# cube_bottom_3.net
KiCad netlist of a schematic drawn in EAGLE
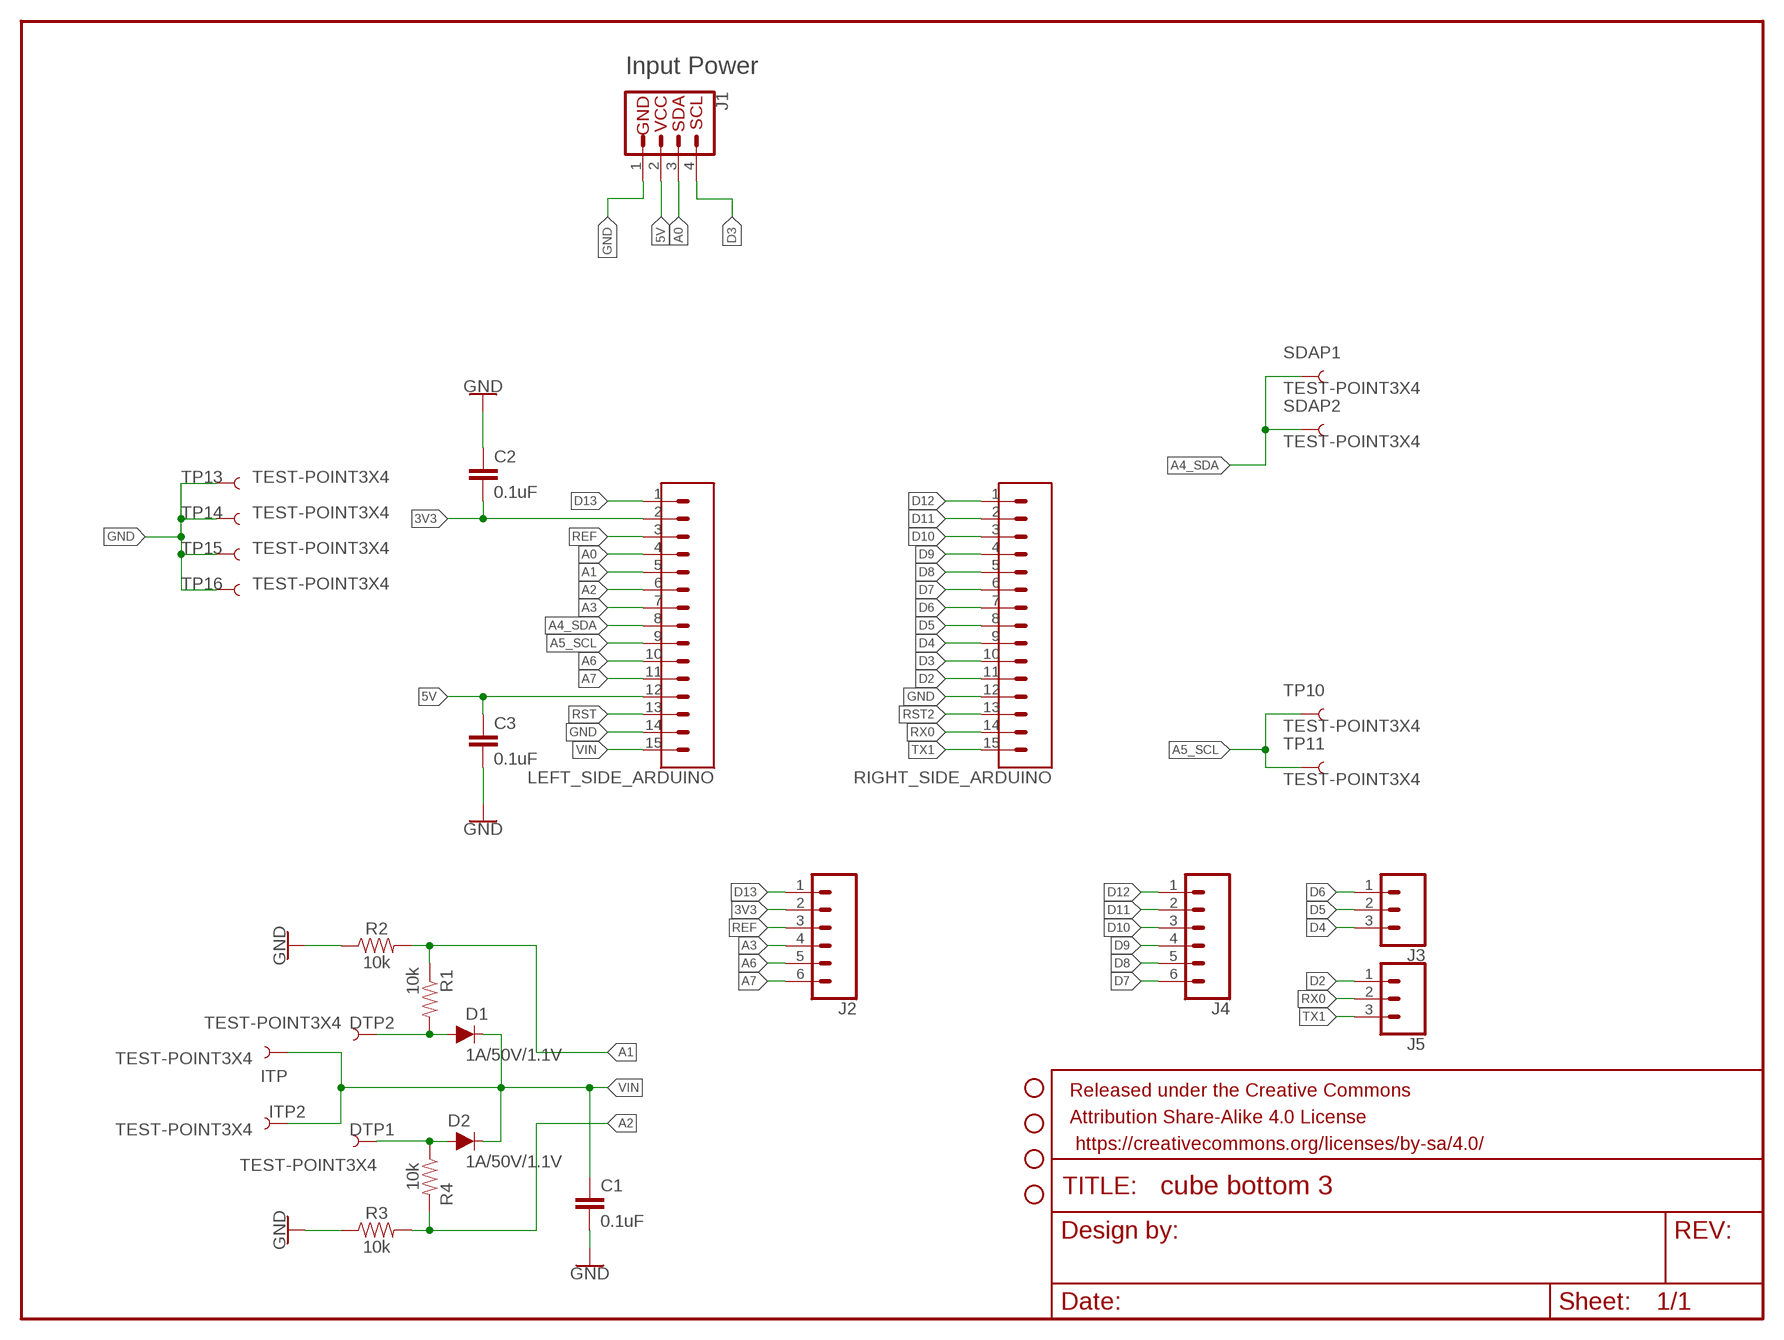
[diagram p0: schematic, sheet 1]

(export (version "E")
  (design (tool "Eeschema 10.0.6"))
  (components
    (comp (ref "C1")
      (value "0.1uF")
      (footprint "eagle-import:0603")
      (libsource (lib "eagle-import") (part "0.1UF-0603-25V-5%"))
    )
    (comp (ref "C2")
      (value "0.1uF")
      (footprint "eagle-import:0603")
      (libsource (lib "eagle-import") (part "0.1UF-0603-25V-(+80/-20%)"))
    )
    (comp (ref "C3")
      (value "0.1uF")
      (footprint "eagle-import:0603")
      (libsource (lib "eagle-import") (part "0.1UF-0603-25V-(+80/-20%)"))
    )
    (comp (ref "D1")
      (value "1A/50V/1.1V")
      (footprint "eagle-import:DIODE-1N4001")
      (libsource (lib "eagle-import") (part "DIODE-PTH"))
    )
    (comp (ref "D2")
      (value "1A/50V/1.1V")
      (footprint "eagle-import:DIODE-1N4001")
      (libsource (lib "eagle-import") (part "DIODE-PTH"))
    )
    (comp (ref "DTP1")
      (value "TEST-POINT3X4")
      (footprint "eagle-import:PAD.03X.04")
      (libsource (lib "eagle-import") (part "TEST-POINT3X4"))
    )
    (comp (ref "DTP2")
      (value "TEST-POINT3X4")
      (footprint "eagle-import:PAD.03X.04")
      (libsource (lib "eagle-import") (part "TEST-POINT3X4"))
    )
    (comp (ref "FRAME1")
      (value "FRAME-LETTERNO_PACKAGE")
      (footprint "eagle-import:DUMMY")
      (fields (field (name "DESIGNER") "Nobody"))
      (libsource (lib "eagle-import") (part "FRAME-LETTERNO_PACKAGE"))
    )
    (comp (ref "H1")
      (value "STAND-OFF")
      (footprint "eagle-import:STAND-OFF")
      (libsource (lib "eagle-import") (part "STAND-OFF"))
    )
    (comp (ref "H2")
      (value "STAND-OFF")
      (footprint "eagle-import:STAND-OFF")
      (libsource (lib "eagle-import") (part "STAND-OFF"))
    )
    (comp (ref "H3")
      (value "STAND-OFF")
      (footprint "eagle-import:STAND-OFF")
      (libsource (lib "eagle-import") (part "STAND-OFF"))
    )
    (comp (ref "H4")
      (value "STAND-OFF")
      (footprint "eagle-import:STAND-OFF")
      (libsource (lib "eagle-import") (part "STAND-OFF"))
    )
    (comp (ref "ITP")
      (value "TEST-POINT3X4")
      (footprint "eagle-import:PAD.03X.04")
      (libsource (lib "eagle-import") (part "TEST-POINT3X4"))
    )
    (comp (ref "ITP2")
      (value "TEST-POINT3X4")
      (footprint "eagle-import:PAD.03X.04")
      (libsource (lib "eagle-import") (part "TEST-POINT3X4"))
    )
    (comp (ref "J1")
      (value "QWIIC_CONNECTORJS-1MM")
      (footprint "eagle-import:1X04_1MM_RA")
      (libsource (lib "eagle-import") (part "QWIIC_CONNECTORJS-1MM"))
    )
    (comp (ref "J2")
      (value "CONN_06SILK_FEMALE_PTH")
      (footprint "eagle-import:1X06")
      (libsource (lib "eagle-import") (part "CONN_06SILK_FEMALE_PTH"))
    )
    (comp (ref "J3")
      (value "CONN_03")
      (footprint "eagle-import:1X03")
      (libsource (lib "eagle-import") (part "CONN_03"))
    )
    (comp (ref "J4")
      (value "CONN_06SILK_FEMALE_PTH")
      (footprint "eagle-import:1X06")
      (libsource (lib "eagle-import") (part "CONN_06SILK_FEMALE_PTH"))
    )
    (comp (ref "J5")
      (value "CONN_03")
      (footprint "eagle-import:1X03")
      (libsource (lib "eagle-import") (part "CONN_03"))
    )
    (comp (ref "LEFT_SIDE_ARDUINO")
      (value "CONN_06SMD_MALE")
      (footprint "eagle-import:1X15_SMD_MALE")
      (libsource (lib "eagle-import") (part "capstone footprints_CONN_06SMD_MALE"))
    )
    (comp (ref "R1")
      (value "10k")
      (footprint "eagle-import:0603")
      (libsource (lib "eagle-import") (part "10KOHM-0603-1/10W-1%"))
    )
    (comp (ref "R2")
      (value "10k")
      (footprint "eagle-import:0603")
      (libsource (lib "eagle-import") (part "10KOHM-0603-1/10W-1%"))
    )
    (comp (ref "R3")
      (value "10k")
      (footprint "eagle-import:0603")
      (libsource (lib "eagle-import") (part "10KOHM-0603-1/10W-1%"))
    )
    (comp (ref "R4")
      (value "10k")
      (footprint "eagle-import:0603")
      (libsource (lib "eagle-import") (part "10KOHM-0603-1/10W-1%"))
    )
    (comp (ref "RIGHT_SIDE_ARDUINO")
      (value "CONN_06SMD_MALE")
      (footprint "eagle-import:1X15_SMD_MALE")
      (libsource (lib "eagle-import") (part "capstone footprints_CONN_06SMD_MALE"))
    )
    (comp (ref "SDAP1")
      (value "TEST-POINT3X4")
      (footprint "eagle-import:PAD.03X.04")
      (libsource (lib "eagle-import") (part "TEST-POINT3X4"))
    )
    (comp (ref "SDAP2")
      (value "TEST-POINT3X4")
      (footprint "eagle-import:PAD.03X.04")
      (libsource (lib "eagle-import") (part "TEST-POINT3X4"))
    )
    (comp (ref "TP10")
      (value "TEST-POINT3X4")
      (footprint "eagle-import:PAD.03X.04")
      (libsource (lib "eagle-import") (part "TEST-POINT3X4"))
    )
    (comp (ref "TP11")
      (value "TEST-POINT3X4")
      (footprint "eagle-import:PAD.03X.04")
      (libsource (lib "eagle-import") (part "TEST-POINT3X4"))
    )
    (comp (ref "TP13")
      (value "TEST-POINT3X4")
      (footprint "eagle-import:PAD.03X.04")
      (libsource (lib "eagle-import") (part "TEST-POINT3X4"))
    )
    (comp (ref "TP14")
      (value "TEST-POINT3X4")
      (footprint "eagle-import:PAD.03X.04")
      (libsource (lib "eagle-import") (part "TEST-POINT3X4"))
    )
    (comp (ref "TP15")
      (value "TEST-POINT3X4")
      (footprint "eagle-import:PAD.03X.04")
      (libsource (lib "eagle-import") (part "TEST-POINT3X4"))
    )
    (comp (ref "TP16")
      (value "TEST-POINT3X4")
      (footprint "eagle-import:PAD.03X.04")
      (libsource (lib "eagle-import") (part "TEST-POINT3X4"))
    )
  )
  (nets
    (net (code "1") (name "3V3") (class "Default")
      (node (ref "C2") (pin "2") (pinfunction "2_2") (pintype "passive"))
      (node (ref "J2") (pin "2") (pinfunction "2_2") (pintype "passive"))
      (node (ref "LEFT_SIDE_ARDUINO") (pin "2") (pinfunction "2_2") (pintype "passive"))
    )
    (net (code "2") (name "5V") (class "Default")
      (node (ref "C3") (pin "1") (pinfunction "1_1") (pintype "passive"))
      (node (ref "J1") (pin "2") (pinfunction "VCC_2") (pintype "power_in"))
      (node (ref "LEFT_SIDE_ARDUINO") (pin "12") (pinfunction "12_12") (pintype "passive"))
    )
    (net (code "3") (name "A0") (class "Default")
      (node (ref "J1") (pin "3") (pinfunction "SDA_3") (pintype "passive"))
      (node (ref "LEFT_SIDE_ARDUINO") (pin "4") (pinfunction "4_4") (pintype "passive"))
    )
    (net (code "4") (name "A1") (class "Default")
      (node (ref "LEFT_SIDE_ARDUINO") (pin "5") (pinfunction "5_5") (pintype "passive"))
      (node (ref "R1") (pin "1") (pinfunction "1_1") (pintype "passive"))
      (node (ref "R2") (pin "2") (pinfunction "2_2") (pintype "passive"))
    )
    (net (code "5") (name "A2") (class "Default")
      (node (ref "LEFT_SIDE_ARDUINO") (pin "6") (pinfunction "6_6") (pintype "passive"))
      (node (ref "R3") (pin "2") (pinfunction "2_2") (pintype "passive"))
      (node (ref "R4") (pin "2") (pinfunction "2_2") (pintype "passive"))
    )
    (net (code "6") (name "A3") (class "Default")
      (node (ref "J2") (pin "4") (pinfunction "4_4") (pintype "passive"))
      (node (ref "LEFT_SIDE_ARDUINO") (pin "7") (pinfunction "7_7") (pintype "passive"))
    )
    (net (code "7") (name "A4_SDA") (class "Default")
      (node (ref "LEFT_SIDE_ARDUINO") (pin "8") (pinfunction "8_8") (pintype "passive"))
      (node (ref "SDAP1") (pin "P$1") (pinfunction "1_P$1") (pintype "bidirectional"))
      (node (ref "SDAP2") (pin "P$1") (pinfunction "1_P$1") (pintype "bidirectional"))
    )
    (net (code "8") (name "A5_SCL") (class "Default")
      (node (ref "LEFT_SIDE_ARDUINO") (pin "9") (pinfunction "9_9") (pintype "passive"))
      (node (ref "TP10") (pin "P$1") (pinfunction "1_P$1") (pintype "bidirectional"))
      (node (ref "TP11") (pin "P$1") (pinfunction "1_P$1") (pintype "bidirectional"))
    )
    (net (code "9") (name "A6") (class "Default")
      (node (ref "J2") (pin "5") (pinfunction "5_5") (pintype "passive"))
      (node (ref "LEFT_SIDE_ARDUINO") (pin "10") (pinfunction "10_10") (pintype "passive"))
    )
    (net (code "10") (name "A7") (class "Default")
      (node (ref "J2") (pin "6") (pinfunction "6_6") (pintype "passive"))
      (node (ref "LEFT_SIDE_ARDUINO") (pin "11") (pinfunction "11_11") (pintype "passive"))
    )
    (net (code "11") (name "D2") (class "Default")
      (node (ref "J5") (pin "1") (pinfunction "1_1") (pintype "passive"))
      (node (ref "RIGHT_SIDE_ARDUINO") (pin "11") (pinfunction "11_11") (pintype "passive"))
    )
    (net (code "12") (name "D3") (class "Default")
      (node (ref "J1") (pin "4") (pinfunction "SCL_4") (pintype "passive"))
      (node (ref "RIGHT_SIDE_ARDUINO") (pin "10") (pinfunction "10_10") (pintype "passive"))
    )
    (net (code "13") (name "D4") (class "Default")
      (node (ref "J3") (pin "3") (pinfunction "3_3") (pintype "passive"))
      (node (ref "RIGHT_SIDE_ARDUINO") (pin "9") (pinfunction "9_9") (pintype "passive"))
    )
    (net (code "14") (name "D5") (class "Default")
      (node (ref "J3") (pin "2") (pinfunction "2_2") (pintype "passive"))
      (node (ref "RIGHT_SIDE_ARDUINO") (pin "8") (pinfunction "8_8") (pintype "passive"))
    )
    (net (code "15") (name "D6") (class "Default")
      (node (ref "J3") (pin "1") (pinfunction "1_1") (pintype "passive"))
      (node (ref "RIGHT_SIDE_ARDUINO") (pin "7") (pinfunction "7_7") (pintype "passive"))
    )
    (net (code "16") (name "D7") (class "Default")
      (node (ref "J4") (pin "6") (pinfunction "6_6") (pintype "passive"))
      (node (ref "RIGHT_SIDE_ARDUINO") (pin "6") (pinfunction "6_6") (pintype "passive"))
    )
    (net (code "17") (name "D8") (class "Default")
      (node (ref "J4") (pin "5") (pinfunction "5_5") (pintype "passive"))
      (node (ref "RIGHT_SIDE_ARDUINO") (pin "5") (pinfunction "5_5") (pintype "passive"))
    )
    (net (code "18") (name "D9") (class "Default")
      (node (ref "J4") (pin "4") (pinfunction "4_4") (pintype "passive"))
      (node (ref "RIGHT_SIDE_ARDUINO") (pin "4") (pinfunction "4_4") (pintype "passive"))
    )
    (net (code "19") (name "D10") (class "Default")
      (node (ref "J4") (pin "3") (pinfunction "3_3") (pintype "passive"))
      (node (ref "RIGHT_SIDE_ARDUINO") (pin "3") (pinfunction "3_3") (pintype "passive"))
    )
    (net (code "20") (name "D11") (class "Default")
      (node (ref "J4") (pin "2") (pinfunction "2_2") (pintype "passive"))
      (node (ref "RIGHT_SIDE_ARDUINO") (pin "2") (pinfunction "2_2") (pintype "passive"))
    )
    (net (code "21") (name "D12") (class "Default")
      (node (ref "J4") (pin "1") (pinfunction "1_1") (pintype "passive"))
      (node (ref "RIGHT_SIDE_ARDUINO") (pin "1") (pinfunction "1_1") (pintype "passive"))
    )
    (net (code "22") (name "D13") (class "Default")
      (node (ref "J2") (pin "1") (pinfunction "1_1") (pintype "passive"))
      (node (ref "LEFT_SIDE_ARDUINO") (pin "1") (pinfunction "1_1") (pintype "passive"))
    )
    (net (code "23") (name "GND") (class "Default")
      (node (ref "C1") (pin "2") (pinfunction "2_2") (pintype "passive"))
      (node (ref "C2") (pin "1") (pinfunction "1_1") (pintype "passive"))
      (node (ref "C3") (pin "2") (pinfunction "2_2") (pintype "passive"))
      (node (ref "J1") (pin "1") (pinfunction "GND_1") (pintype "power_in"))
      (node (ref "LEFT_SIDE_ARDUINO") (pin "14") (pinfunction "14_14") (pintype "passive"))
      (node (ref "R2") (pin "1") (pinfunction "1_1") (pintype "passive"))
      (node (ref "R3") (pin "1") (pinfunction "1_1") (pintype "passive"))
      (node (ref "RIGHT_SIDE_ARDUINO") (pin "12") (pinfunction "12_12") (pintype "passive"))
      (node (ref "TP13") (pin "P$1") (pinfunction "1_P$1") (pintype "bidirectional"))
      (node (ref "TP14") (pin "P$1") (pinfunction "1_P$1") (pintype "bidirectional"))
      (node (ref "TP15") (pin "P$1") (pinfunction "1_P$1") (pintype "bidirectional"))
      (node (ref "TP16") (pin "P$1") (pinfunction "1_P$1") (pintype "bidirectional"))
    )
    (net (code "24") (name "Net-(DTP1-1)") (class "Default")
      (node (ref "D2") (pin "A") (pinfunction "A_A") (pintype "passive"))
      (node (ref "DTP1") (pin "P$1") (pinfunction "1_P$1") (pintype "bidirectional"))
      (node (ref "R4") (pin "1") (pinfunction "1_1") (pintype "passive"))
    )
    (net (code "25") (name "Net-(DTP2-1)") (class "Default")
      (node (ref "D1") (pin "A") (pinfunction "A_A") (pintype "passive"))
      (node (ref "DTP2") (pin "P$1") (pinfunction "1_P$1") (pintype "bidirectional"))
      (node (ref "R1") (pin "2") (pinfunction "2_2") (pintype "passive"))
    )
    (net (code "26") (name "REF") (class "Default")
      (node (ref "J2") (pin "3") (pinfunction "3_3") (pintype "passive"))
      (node (ref "LEFT_SIDE_ARDUINO") (pin "3") (pinfunction "3_3") (pintype "passive"))
    )
    (net (code "27") (name "RST") (class "Default")
      (node (ref "LEFT_SIDE_ARDUINO") (pin "13") (pinfunction "13_13") (pintype "passive"))
    )
    (net (code "28") (name "RST2") (class "Default")
      (node (ref "RIGHT_SIDE_ARDUINO") (pin "13") (pinfunction "13_13") (pintype "passive"))
    )
    (net (code "29") (name "RX0") (class "Default")
      (node (ref "J5") (pin "2") (pinfunction "2_2") (pintype "passive"))
      (node (ref "RIGHT_SIDE_ARDUINO") (pin "14") (pinfunction "14_14") (pintype "passive"))
    )
    (net (code "30") (name "TX1") (class "Default")
      (node (ref "J5") (pin "3") (pinfunction "3_3") (pintype "passive"))
      (node (ref "RIGHT_SIDE_ARDUINO") (pin "15") (pinfunction "15_15") (pintype "passive"))
    )
    (net (code "31") (name "VIN") (class "Default")
      (node (ref "C1") (pin "1") (pinfunction "1_1") (pintype "passive"))
      (node (ref "D1") (pin "C") (pinfunction "C_C") (pintype "passive"))
      (node (ref "D2") (pin "C") (pinfunction "C_C") (pintype "passive"))
      (node (ref "ITP") (pin "P$1") (pinfunction "1_P$1") (pintype "bidirectional"))
      (node (ref "ITP2") (pin "P$1") (pinfunction "1_P$1") (pintype "bidirectional"))
      (node (ref "LEFT_SIDE_ARDUINO") (pin "15") (pinfunction "15_15") (pintype "passive"))
    )
  )
)
